# ProDoc_HackerCard_2025-08-16.net
KiCad netlist of a schematic drawn in EasyEDA Pro
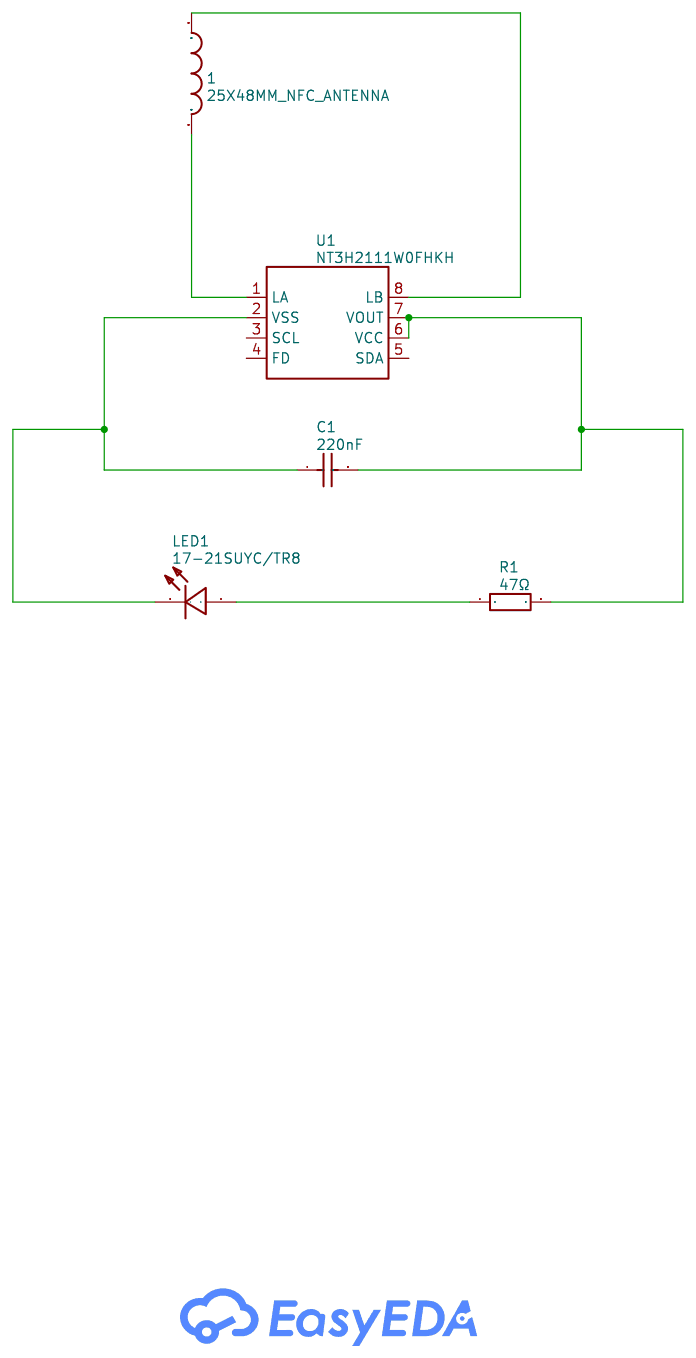
[diagram p0: schematic sheet]

(export (version "E")
  (design (tool "Eeschema 10.0.6"))
  (components
    (comp (ref "1")
      (value "25X48MM_NFC_ANTENNA")
      (fields (field (name "Contributor") "dnonoo"))
      (libsource (lib "easyedapro") (part "25X48MM_NFC_ANTENNA"))
    )
    (comp (ref "C1")
      (value "220nF")
      (footprint "easyedapro:C0603")
      (fields
        (field (name "Manufacturer Part") "CL10B224KA8NNNC")
        (field (name "Manufacturer") "SAMSUNG(三星)")
      )
      (libsource (lib "easyedapro") (part "220nF"))
    )
    (comp (ref "LED1")
      (value "17-21SUYC/TR8")
      (footprint "easyedapro:LED0805-R-RD")
      (fields (field (name "Manufacturer Part") "KT-0805黄灯") (field (name "Manufacturer") "KENTO"))
      (libsource (lib "easyedapro") (part "17-21SUYC/TR8"))
    )
    (comp (ref "R1")
      (value "47Ω")
      (footprint "easyedapro:R0603")
      (fields
        (field (name "Manufacturer Part") "0603WAF470JT5E")
        (field (name "Manufacturer") "UNI-ROYAL(厚声)")
      )
      (libsource (lib "easyedapro") (part "47Ω"))
    )
    (comp (ref "U1")
      (value "NT3H2111W0FHKH")
      (footprint "easyedapro:XQFN-8_L1.6-W1.6-P0.50-BL_NT3H2111W0FHKH")
      (fields (field (name "Manufacturer") "NXP(恩智浦)") (field (name "Contributor") "LCSC"))
      (libsource (lib "easyedapro") (part "NT3H2111W0FHKH"))
    )
  )
  (nets
    (net (code "1") (name "Net-(LED1-+)") (class "Default")
      (node (ref "LED1") (pin "1") (pinfunction "+_1") (pintype "unspecified"))
      (node (ref "R1") (pin "1") (pinfunction "1_1") (pintype "input"))
    )
    (net (code "2") (name "Net-(LED1--)") (class "Default")
      (node (ref "C1") (pin "1") (pinfunction "1_1") (pintype "input"))
      (node (ref "LED1") (pin "2") (pinfunction "-_2") (pintype "unspecified"))
      (node (ref "U1") (pin "2") (pinfunction "VSS_2") (pintype "unspecified"))
    )
    (net (code "3") (name "Net-(U1-LA)") (class "Default")
      (node (ref "1") (pin "P$2") (pinfunction "P$2_P$2") (pintype "bidirectional"))
      (node (ref "U1") (pin "1") (pinfunction "LA_1") (pintype "unspecified"))
    )
    (net (code "4") (name "Net-(U1-LB)") (class "Default")
      (node (ref "1") (pin "P$1") (pinfunction "P$1_P$1") (pintype "bidirectional"))
      (node (ref "U1") (pin "8") (pinfunction "LB_8") (pintype "unspecified"))
    )
    (net (code "5") (name "Net-(U1-VCC)") (class "Default")
      (node (ref "C1") (pin "2") (pinfunction "2_2") (pintype "input"))
      (node (ref "R1") (pin "2") (pinfunction "2_2") (pintype "input"))
      (node (ref "U1") (pin "6") (pinfunction "VCC_6") (pintype "unspecified"))
      (node (ref "U1") (pin "7") (pinfunction "VOUT_7") (pintype "unspecified"))
    )
    (net (code "6") (name "unconnected-(U1-FD-Pad4)") (class "Default")
      (node (ref "U1") (pin "4") (pinfunction "FD_4") (pintype "unspecified"))
    )
    (net (code "7") (name "unconnected-(U1-SCL-Pad3)") (class "Default")
      (node (ref "U1") (pin "3") (pinfunction "SCL_3") (pintype "unspecified"))
    )
    (net (code "8") (name "unconnected-(U1-SDA-Pad5)") (class "Default")
      (node (ref "U1") (pin "5") (pinfunction "SDA_5") (pintype "unspecified"))
    )
  )
)
